# LedMatrixPixel.net
KiCad netlist of a schematic drawn in Altium Designer
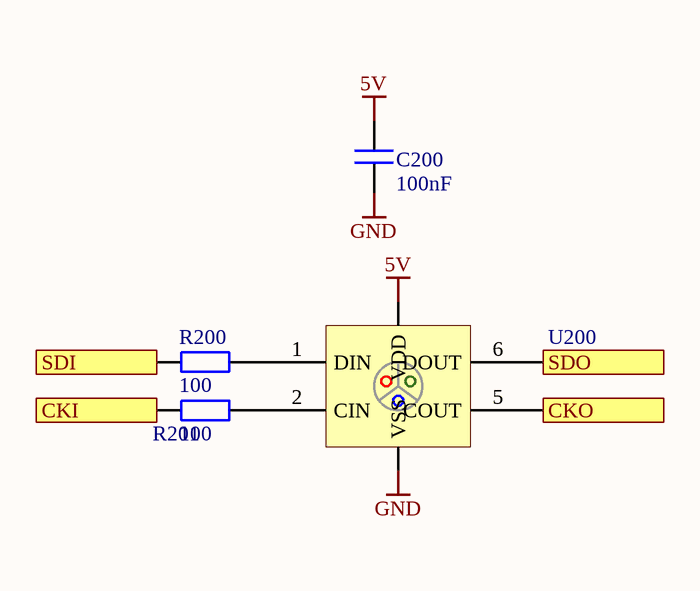
[diagram p0: LedMatrixPixel.SchDoc]

(export (version "E")
  (design (tool "Eeschema 10.0.6"))
  (components
    (comp (ref "C200")
      (value "100nF")
      (footprint "CAP1608X06M")
      (libsource (lib "ColorSensor") (part "Capacitor 100n"))
    )
    (comp (ref "R200")
      (value "100")
      (footprint "RESC1608X06M")
      (libsource (lib "ColorSensor") (part "Resistor 100"))
    )
    (comp (ref "R201")
      (value "100")
      (footprint "RESC1608X06M")
      (libsource (lib "ColorSensor") (part "Resistor 100"))
    )
    (comp (ref "U200")
      (value "APA102-2020")
      (footprint "APA102")
      (description "RGB LED")
      (libsource (lib "LedMatrix") (part "APA102-2020"))
    )
  )
  (nets
    (net (code "1") (name "/CKI") (class "Default")
      (node (ref "R201") (pin "1") (pinfunction "1_1") (pintype "passive"))
    )
    (net (code "2") (name "/CKO") (class "Default")
      (node (ref "U200") (pin "5") (pinfunction "COUT_5") (pintype "passive"))
    )
    (net (code "3") (name "/SDI") (class "Default")
      (node (ref "R200") (pin "1") (pinfunction "1_1") (pintype "passive"))
    )
    (net (code "4") (name "/SDO") (class "Default")
      (node (ref "U200") (pin "6") (pinfunction "DOUT_6") (pintype "passive"))
    )
    (net (code "5") (name "5V") (class "Default")
      (node (ref "C200") (pin "2") (pinfunction "2_2") (pintype "passive"))
      (node (ref "U200") (pin "4") (pinfunction "VDD_4") (pintype "passive"))
    )
    (net (code "6") (name "GND") (class "Default")
      (node (ref "C200") (pin "1") (pinfunction "1_1") (pintype "passive"))
      (node (ref "U200") (pin "3") (pinfunction "VSS_3") (pintype "passive"))
    )
    (net (code "7") (name "Net-(U200-CIN)") (class "Default")
      (node (ref "R201") (pin "2") (pinfunction "2_2") (pintype "passive"))
      (node (ref "U200") (pin "2") (pinfunction "CIN_2") (pintype "passive"))
    )
    (net (code "8") (name "Net-(U200-DIN)") (class "Default")
      (node (ref "R200") (pin "2") (pinfunction "2_2") (pintype "passive"))
      (node (ref "U200") (pin "1") (pinfunction "DIN_1") (pintype "passive"))
    )
  )
)
